# schem.net
KiCad netlist of a schematic drawn in EAGLE
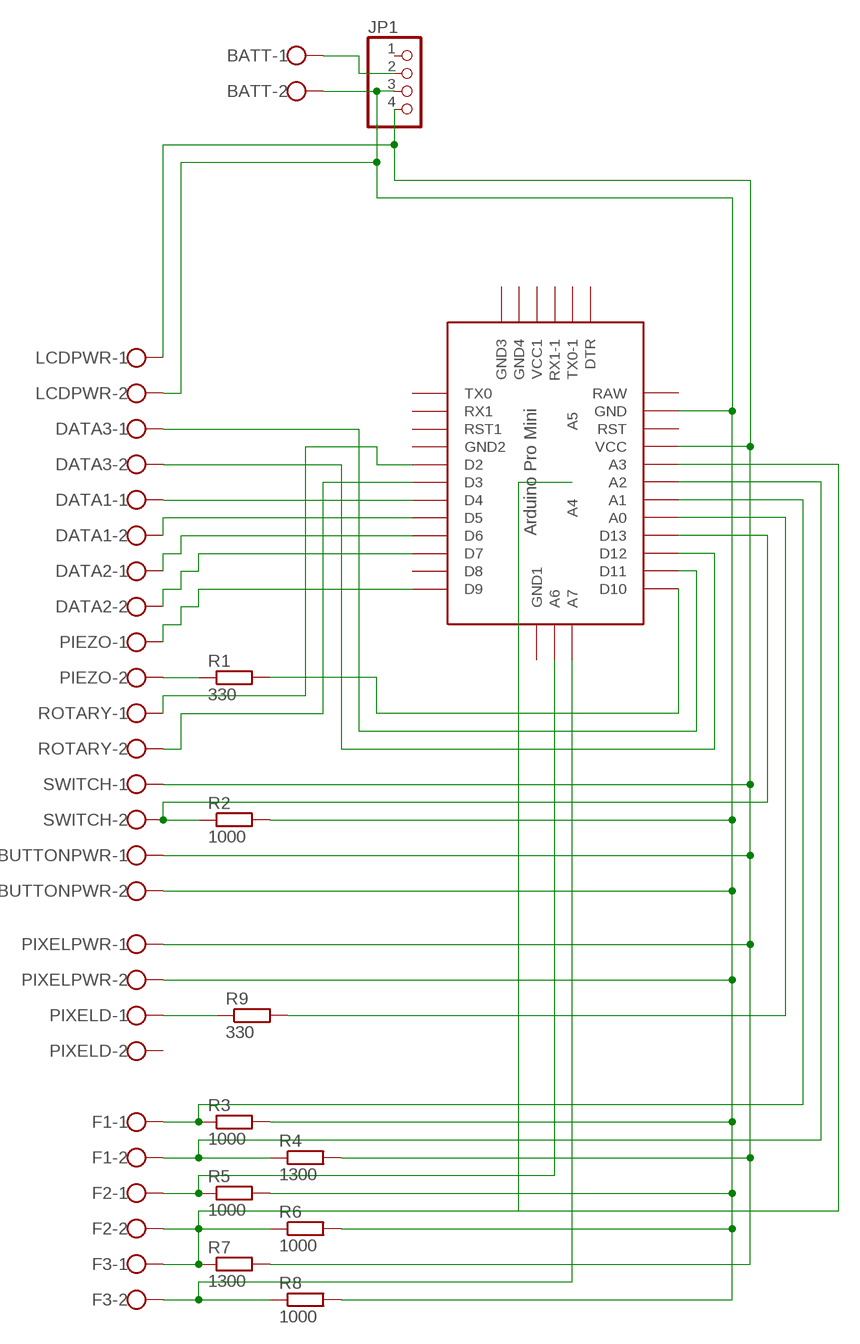
[diagram p0: schematic, sheet 1]

(export (version "E")
  (design (tool "Eeschema 10.0.6"))
  (components
    (comp (ref "BATT")
      (value "W237-102")
      (footprint "eagle-import:W237-102")
      (fields (field (name "MPN") "237-102"))
      (libsource (lib "eagle-import") (part "W237-102"))
    )
    (comp (ref "BUTTONPWR")
      (value "W237-102")
      (footprint "eagle-import:W237-102")
      (fields (field (name "MPN") "237-102"))
      (libsource (lib "eagle-import") (part "W237-102"))
    )
    (comp (ref "DATA1")
      (value "W237-102")
      (footprint "eagle-import:W237-102")
      (fields (field (name "MPN") "237-102"))
      (libsource (lib "eagle-import") (part "W237-102"))
    )
    (comp (ref "DATA2")
      (value "W237-102")
      (footprint "eagle-import:W237-102")
      (fields (field (name "MPN") "237-102"))
      (libsource (lib "eagle-import") (part "W237-102"))
    )
    (comp (ref "DATA3")
      (value "W237-102")
      (footprint "eagle-import:W237-102")
      (fields (field (name "MPN") "237-102"))
      (libsource (lib "eagle-import") (part "W237-102"))
    )
    (comp (ref "F1")
      (value "W237-102")
      (footprint "eagle-import:W237-102")
      (fields (field (name "MPN") "237-102"))
      (libsource (lib "eagle-import") (part "W237-102"))
    )
    (comp (ref "F2")
      (value "W237-102")
      (footprint "eagle-import:W237-102")
      (fields (field (name "MPN") "237-102"))
      (libsource (lib "eagle-import") (part "W237-102"))
    )
    (comp (ref "F3")
      (value "W237-102")
      (footprint "eagle-import:W237-102")
      (fields (field (name "MPN") "237-102"))
      (libsource (lib "eagle-import") (part "W237-102"))
    )
    (comp (ref "JP1")
      (value "PINHD-1X4")
      (footprint "eagle-import:1X04")
      (libsource (lib "eagle-import") (part "PINHD-1X4"))
    )
    (comp (ref "LCDPWR")
      (value "W237-102")
      (footprint "eagle-import:W237-102")
      (fields (field (name "MPN") "237-102"))
      (libsource (lib "eagle-import") (part "W237-102"))
    )
    (comp (ref "PIEZO")
      (value "W237-102")
      (footprint "eagle-import:W237-102")
      (fields (field (name "MPN") "237-102"))
      (libsource (lib "eagle-import") (part "W237-102"))
    )
    (comp (ref "PIXELD")
      (value "W237-102")
      (footprint "eagle-import:W237-102")
      (fields (field (name "MPN") "237-102"))
      (libsource (lib "eagle-import") (part "W237-102"))
    )
    (comp (ref "PIXELPWR")
      (value "W237-102")
      (footprint "eagle-import:W237-102")
      (fields (field (name "MPN") "237-102"))
      (libsource (lib "eagle-import") (part "W237-102"))
    )
    (comp (ref "R1")
      (value "330")
      (footprint "eagle-import:0204_7")
      (libsource (lib "eagle-import") (part "R-EU_0204/7"))
    )
    (comp (ref "R2")
      (value "1000")
      (footprint "eagle-import:0204_7")
      (libsource (lib "eagle-import") (part "R-EU_0204/7"))
    )
    (comp (ref "R3")
      (value "1000")
      (footprint "eagle-import:0204_7")
      (libsource (lib "eagle-import") (part "R-EU_0204/7"))
    )
    (comp (ref "R4")
      (value "1300")
      (footprint "eagle-import:0204_7")
      (libsource (lib "eagle-import") (part "R-EU_0204/7"))
    )
    (comp (ref "R5")
      (value "1000")
      (footprint "eagle-import:0204_7")
      (libsource (lib "eagle-import") (part "R-EU_0204/7"))
    )
    (comp (ref "R6")
      (value "1000")
      (footprint "eagle-import:0204_7")
      (libsource (lib "eagle-import") (part "R-EU_0204/7"))
    )
    (comp (ref "R7")
      (value "1300")
      (footprint "eagle-import:0204_7")
      (libsource (lib "eagle-import") (part "R-EU_0204/7"))
    )
    (comp (ref "R8")
      (value "1000")
      (footprint "eagle-import:0204_7")
      (libsource (lib "eagle-import") (part "R-EU_0204/7"))
    )
    (comp (ref "R9")
      (value "330")
      (footprint "eagle-import:0207_10")
      (libsource (lib "eagle-import") (part "R-EU_0207/10"))
    )
    (comp (ref "ROTARY")
      (value "W237-102")
      (footprint "eagle-import:W237-102")
      (fields (field (name "MPN") "237-102"))
      (libsource (lib "eagle-import") (part "W237-102"))
    )
    (comp (ref "SWITCH")
      (value "W237-102")
      (footprint "eagle-import:W237-102")
      (fields (field (name "MPN") "237-102"))
      (libsource (lib "eagle-import") (part "W237-102"))
    )
    (comp (ref "U$1")
      (value "ABK-PRO-MINI")
      (footprint "eagle-import:ABK-PRO-MINI")
      (libsource (lib "eagle-import") (part "ABK-PRO-MINI"))
    )
  )
  (nets
    (net (code "1") (name "Net-(BATTA-KL)") (class "Default")
      (node (ref "BATT") (pin "1") (pinfunction "KL_1") (pintype "passive"))
      (node (ref "JP1") (pin "2") (pinfunction "2_2") (pintype "passive"))
    )
    (net (code "2") (name "Net-(BATTB-KL)") (class "Default")
      (node (ref "BATT") (pin "2") (pinfunction "KL_2") (pintype "passive"))
      (node (ref "BUTTONPWR") (pin "2") (pinfunction "KL_2") (pintype "passive"))
      (node (ref "JP1") (pin "3") (pinfunction "3_3") (pintype "passive"))
      (node (ref "LCDPWR") (pin "2") (pinfunction "KL_2") (pintype "passive"))
      (node (ref "PIXELPWR") (pin "2") (pinfunction "KL_2") (pintype "passive"))
      (node (ref "R2") (pin "2") (pinfunction "2_2") (pintype "passive"))
      (node (ref "R3") (pin "2") (pinfunction "2_2") (pintype "passive"))
      (node (ref "R5") (pin "2") (pinfunction "2_2") (pintype "passive"))
      (node (ref "R6") (pin "2") (pinfunction "2_2") (pintype "passive"))
      (node (ref "R8") (pin "2") (pinfunction "2_2") (pintype "passive"))
      (node (ref "U$1") (pin "GND") (pinfunction "GND_GND") (pintype "bidirectional"))
    )
    (net (code "3") (name "Net-(BUTTONPWRA-KL)") (class "Default")
      (node (ref "BUTTONPWR") (pin "1") (pinfunction "KL_1") (pintype "passive"))
      (node (ref "JP1") (pin "4") (pinfunction "4_4") (pintype "passive"))
      (node (ref "LCDPWR") (pin "1") (pinfunction "KL_1") (pintype "passive"))
      (node (ref "PIXELPWR") (pin "1") (pinfunction "KL_1") (pintype "passive"))
      (node (ref "R4") (pin "2") (pinfunction "2_2") (pintype "passive"))
      (node (ref "R7") (pin "2") (pinfunction "2_2") (pintype "passive"))
      (node (ref "SWITCH") (pin "1") (pinfunction "KL_1") (pintype "passive"))
      (node (ref "U$1") (pin "VCC") (pinfunction "VCC_VCC") (pintype "bidirectional"))
    )
    (net (code "4") (name "Net-(DATA1A-KL)") (class "Default")
      (node (ref "DATA1") (pin "1") (pinfunction "KL_1") (pintype "passive"))
      (node (ref "U$1") (pin "D4") (pinfunction "D4_D4") (pintype "bidirectional"))
    )
    (net (code "5") (name "Net-(DATA1B-KL)") (class "Default")
      (node (ref "DATA1") (pin "2") (pinfunction "KL_2") (pintype "passive"))
      (node (ref "U$1") (pin "D5") (pinfunction "D5_D5") (pintype "bidirectional"))
    )
    (net (code "6") (name "Net-(DATA2A-KL)") (class "Default")
      (node (ref "DATA2") (pin "1") (pinfunction "KL_1") (pintype "passive"))
      (node (ref "U$1") (pin "D6") (pinfunction "D6_D6") (pintype "bidirectional"))
    )
    (net (code "7") (name "Net-(DATA2B-KL)") (class "Default")
      (node (ref "DATA2") (pin "2") (pinfunction "KL_2") (pintype "passive"))
      (node (ref "U$1") (pin "D7") (pinfunction "D7_D7") (pintype "bidirectional"))
    )
    (net (code "8") (name "Net-(DATA3A-KL)") (class "Default")
      (node (ref "DATA3") (pin "1") (pinfunction "KL_1") (pintype "passive"))
      (node (ref "U$1") (pin "D11") (pinfunction "D11_D11") (pintype "bidirectional"))
    )
    (net (code "9") (name "Net-(DATA3B-KL)") (class "Default")
      (node (ref "DATA3") (pin "2") (pinfunction "KL_2") (pintype "passive"))
      (node (ref "U$1") (pin "D12") (pinfunction "D12_D12") (pintype "bidirectional"))
    )
    (net (code "10") (name "Net-(F1A-KL)") (class "Default")
      (node (ref "F1") (pin "1") (pinfunction "KL_1") (pintype "passive"))
      (node (ref "R3") (pin "1") (pinfunction "1_1") (pintype "passive"))
      (node (ref "U$1") (pin "A1") (pinfunction "A1_A1") (pintype "bidirectional"))
    )
    (net (code "11") (name "Net-(F1B-KL)") (class "Default")
      (node (ref "F1") (pin "2") (pinfunction "KL_2") (pintype "passive"))
      (node (ref "R4") (pin "1") (pinfunction "1_1") (pintype "passive"))
      (node (ref "U$1") (pin "A2") (pinfunction "A2_A2") (pintype "bidirectional"))
    )
    (net (code "12") (name "Net-(F2A-KL)") (class "Default")
      (node (ref "F2") (pin "1") (pinfunction "KL_1") (pintype "passive"))
      (node (ref "R5") (pin "1") (pinfunction "1_1") (pintype "passive"))
      (node (ref "U$1") (pin "A6") (pinfunction "A6_A6") (pintype "bidirectional"))
    )
    (net (code "13") (name "Net-(F2B-KL)") (class "Default")
      (node (ref "F2") (pin "2") (pinfunction "KL_2") (pintype "passive"))
      (node (ref "F3") (pin "1") (pinfunction "KL_1") (pintype "passive"))
      (node (ref "R6") (pin "1") (pinfunction "1_1") (pintype "passive"))
      (node (ref "R7") (pin "1") (pinfunction "1_1") (pintype "passive"))
      (node (ref "U$1") (pin "A3") (pinfunction "A3_A3") (pintype "bidirectional"))
      (node (ref "U$1") (pin "A4") (pinfunction "A4_A4") (pintype "bidirectional"))
    )
    (net (code "14") (name "Net-(F3B-KL)") (class "Default")
      (node (ref "F3") (pin "2") (pinfunction "KL_2") (pintype "passive"))
      (node (ref "R8") (pin "1") (pinfunction "1_1") (pintype "passive"))
      (node (ref "U$1") (pin "A7") (pinfunction "A7_A7") (pintype "bidirectional"))
    )
    (net (code "15") (name "Net-(PIEZOA-KL)") (class "Default")
      (node (ref "PIEZO") (pin "1") (pinfunction "KL_1") (pintype "passive"))
      (node (ref "U$1") (pin "D9") (pinfunction "D9_D9") (pintype "bidirectional"))
    )
    (net (code "16") (name "Net-(PIEZOB-KL)") (class "Default")
      (node (ref "PIEZO") (pin "2") (pinfunction "KL_2") (pintype "passive"))
      (node (ref "R1") (pin "1") (pinfunction "1_1") (pintype "passive"))
    )
    (net (code "17") (name "Net-(PIXELDA-KL)") (class "Default")
      (node (ref "PIXELD") (pin "1") (pinfunction "KL_1") (pintype "passive"))
      (node (ref "R9") (pin "1") (pinfunction "1_1") (pintype "passive"))
    )
    (net (code "18") (name "Net-(R1-Pad2)") (class "Default")
      (node (ref "R1") (pin "2") (pinfunction "2_2") (pintype "passive"))
      (node (ref "U$1") (pin "D10") (pinfunction "D10_D10") (pintype "bidirectional"))
    )
    (net (code "19") (name "Net-(R9-Pad2)") (class "Default")
      (node (ref "R9") (pin "2") (pinfunction "2_2") (pintype "passive"))
      (node (ref "U$1") (pin "A0") (pinfunction "A0_A0") (pintype "bidirectional"))
    )
    (net (code "20") (name "Net-(ROTARYA-KL)") (class "Default")
      (node (ref "ROTARY") (pin "1") (pinfunction "KL_1") (pintype "passive"))
      (node (ref "U$1") (pin "D2") (pinfunction "D2_D2") (pintype "bidirectional"))
    )
    (net (code "21") (name "Net-(ROTARYB-KL)") (class "Default")
      (node (ref "ROTARY") (pin "2") (pinfunction "KL_2") (pintype "passive"))
      (node (ref "U$1") (pin "D3") (pinfunction "D3_D3") (pintype "bidirectional"))
    )
    (net (code "22") (name "Net-(SWITCHB-KL)") (class "Default")
      (node (ref "R2") (pin "1") (pinfunction "1_1") (pintype "passive"))
      (node (ref "SWITCH") (pin "2") (pinfunction "KL_2") (pintype "passive"))
      (node (ref "U$1") (pin "D13") (pinfunction "D13_D13") (pintype "bidirectional"))
    )
    (net (code "23") (name "unconnected-(JP1-Pad1)") (class "Default")
      (node (ref "JP1") (pin "1") (pinfunction "1_1") (pintype "passive"))
    )
    (net (code "24") (name "unconnected-(PIXELDB-KL-Pad2)") (class "Default")
      (node (ref "PIXELD") (pin "2") (pinfunction "KL_2") (pintype "passive"))
    )
    (net (code "25") (name "unconnected-(U$1-GND1-PadGND4)") (class "Default")
      (node (ref "U$1") (pin "GND4") (pinfunction "GND1_GND4") (pintype "bidirectional"))
    )
    (net (code "26") (name "unconnected-(U$1-GND2-PadGND1)") (class "Default")
      (node (ref "U$1") (pin "GND1") (pinfunction "GND2_GND1") (pintype "bidirectional"))
    )
    (net (code "27") (name "unconnected-(U$1-GND3-PadGND2)") (class "Default")
      (node (ref "U$1") (pin "GND2") (pinfunction "GND3_GND2") (pintype "bidirectional"))
    )
    (net (code "28") (name "unconnected-(U$1-GND4-PadGND3)") (class "Default")
      (node (ref "U$1") (pin "GND3") (pinfunction "GND4_GND3") (pintype "bidirectional"))
    )
    (net (code "29") (name "unconnected-(U$1-PadA5)") (class "Default")
      (node (ref "U$1") (pin "A5") (pinfunction "A5_A5") (pintype "bidirectional"))
    )
    (net (code "30") (name "unconnected-(U$1-PadD8)") (class "Default")
      (node (ref "U$1") (pin "D8") (pinfunction "D8_D8") (pintype "bidirectional"))
    )
    (net (code "31") (name "unconnected-(U$1-PadDTR)") (class "Default")
      (node (ref "U$1") (pin "DTR") (pinfunction "DTR_DTR") (pintype "bidirectional"))
    )
    (net (code "32") (name "unconnected-(U$1-PadRAW)") (class "Default")
      (node (ref "U$1") (pin "RAW") (pinfunction "RAW_RAW") (pintype "bidirectional"))
    )
    (net (code "33") (name "unconnected-(U$1-PadRST)") (class "Default")
      (node (ref "U$1") (pin "RST") (pinfunction "RST_RST") (pintype "bidirectional"))
    )
    (net (code "34") (name "unconnected-(U$1-PadRST1)") (class "Default")
      (node (ref "U$1") (pin "RST1") (pinfunction "RST1_RST1") (pintype "bidirectional"))
    )
    (net (code "35") (name "unconnected-(U$1-PadRX1)") (class "Default")
      (node (ref "U$1") (pin "RX1") (pinfunction "RX1_RX1") (pintype "bidirectional"))
    )
    (net (code "36") (name "unconnected-(U$1-PadRX1-1)") (class "Default")
      (node (ref "U$1") (pin "RX1-1") (pinfunction "RX1-1_RX1-1") (pintype "bidirectional"))
    )
    (net (code "37") (name "unconnected-(U$1-PadTX0)") (class "Default")
      (node (ref "U$1") (pin "TX0") (pinfunction "TX0_TX0") (pintype "bidirectional"))
    )
    (net (code "38") (name "unconnected-(U$1-PadTX0-1)") (class "Default")
      (node (ref "U$1") (pin "TX0-1") (pinfunction "TX0-1_TX0-1") (pintype "bidirectional"))
    )
    (net (code "39") (name "unconnected-(U$1-PadVCC1)") (class "Default")
      (node (ref "U$1") (pin "VCC1") (pinfunction "VCC1_VCC1") (pintype "bidirectional"))
    )
  )
)
